# Tail_lights4.net
KiCad netlist of a schematic drawn in EAGLE
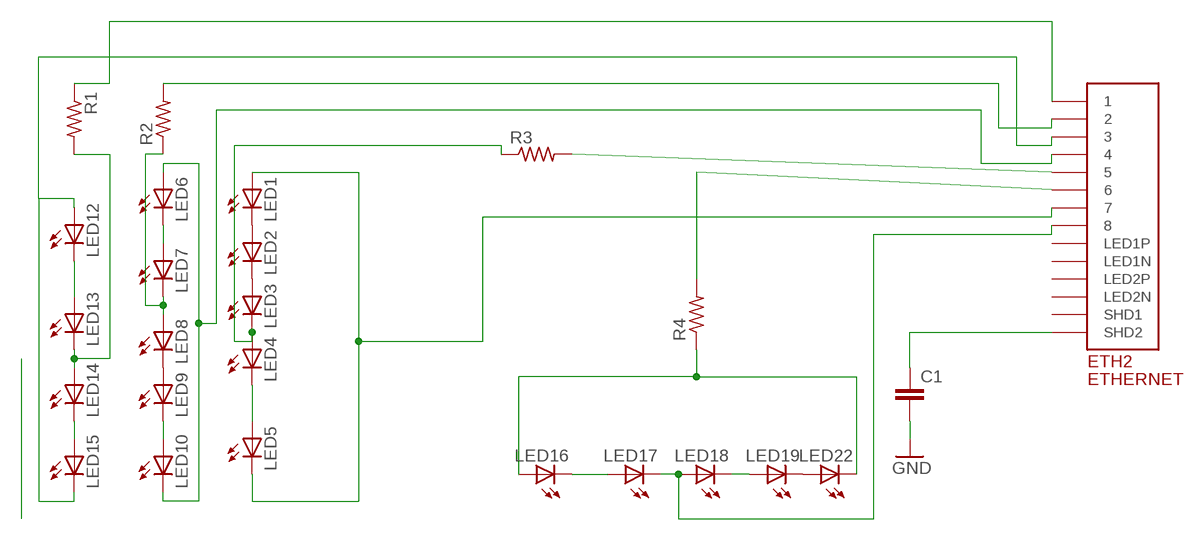
[diagram p0: schematic, sheet 1]

(export (version "E")
  (design (tool "Eeschema 10.0.6"))
  (components
    (comp (ref "C1")
      (value "C2,5-3")
      (footprint "eagle-import:C2.5-3")
      (libsource (lib "eagle-import") (part "C2,5-3"))
    )
    (comp (ref "ETH2")
      (value "ETHERNET")
      (footprint "eagle-import:A122645-ND")
      (libsource (lib "eagle-import") (part "ETHERNET"))
    )
    (comp (ref "LED1")
      (value "LED")
      (footprint "eagle-import:SMARTLED-TTW")
      (libsource (lib "eagle-import") (part "LED"))
    )
    (comp (ref "LED2")
      (value "LED")
      (footprint "eagle-import:SMARTLED-TTW")
      (libsource (lib "eagle-import") (part "LED"))
    )
    (comp (ref "LED3")
      (value "LED")
      (footprint "eagle-import:SMARTLED-TTW")
      (libsource (lib "eagle-import") (part "LED"))
    )
    (comp (ref "LED4")
      (value "LED")
      (footprint "eagle-import:SMARTLED-TTW")
      (libsource (lib "eagle-import") (part "LED"))
    )
    (comp (ref "LED5")
      (value "LED")
      (footprint "eagle-import:SMARTLED-TTW")
      (libsource (lib "eagle-import") (part "LED"))
    )
    (comp (ref "LED6")
      (value "LED")
      (footprint "eagle-import:SMARTLED-TTW")
      (libsource (lib "eagle-import") (part "LED"))
    )
    (comp (ref "LED7")
      (value "LED")
      (footprint "eagle-import:SMARTLED-TTW")
      (libsource (lib "eagle-import") (part "LED"))
    )
    (comp (ref "LED8")
      (value "LED")
      (footprint "eagle-import:SMARTLED-TTW")
      (libsource (lib "eagle-import") (part "LED"))
    )
    (comp (ref "LED9")
      (value "LED")
      (footprint "eagle-import:SMARTLED-TTW")
      (libsource (lib "eagle-import") (part "LED"))
    )
    (comp (ref "LED10")
      (value "LED")
      (footprint "eagle-import:SMARTLED-TTW")
      (libsource (lib "eagle-import") (part "LED"))
    )
    (comp (ref "LED12")
      (value "LED")
      (footprint "eagle-import:SMARTLED-TTW")
      (libsource (lib "eagle-import") (part "LED"))
    )
    (comp (ref "LED13")
      (value "LED")
      (footprint "eagle-import:SMARTLED-TTW")
      (libsource (lib "eagle-import") (part "LED"))
    )
    (comp (ref "LED14")
      (value "LED")
      (footprint "eagle-import:SMARTLED-TTW")
      (libsource (lib "eagle-import") (part "LED"))
    )
    (comp (ref "LED15")
      (value "LED")
      (footprint "eagle-import:SMARTLED-TTW")
      (libsource (lib "eagle-import") (part "LED"))
    )
    (comp (ref "LED16")
      (value "LED")
      (footprint "eagle-import:SMARTLED-TTW")
      (libsource (lib "eagle-import") (part "LED"))
    )
    (comp (ref "LED17")
      (value "LED")
      (footprint "eagle-import:SMARTLED-TTW")
      (libsource (lib "eagle-import") (part "LED"))
    )
    (comp (ref "LED18")
      (value "LED")
      (footprint "eagle-import:SMARTLED-TTW")
      (libsource (lib "eagle-import") (part "LED"))
    )
    (comp (ref "LED19")
      (value "LED")
      (footprint "eagle-import:SMARTLED-TTW")
      (libsource (lib "eagle-import") (part "LED"))
    )
    (comp (ref "LED22")
      (value "LED")
      (footprint "eagle-import:SMARTLED-TTW")
      (libsource (lib "eagle-import") (part "LED"))
    )
    (comp (ref "R1")
      (value "R-US_0204/5")
      (footprint "eagle-import:0204_5")
      (libsource (lib "eagle-import") (part "R-US_0204/5"))
    )
    (comp (ref "R2")
      (value "R-US_0204/2V")
      (footprint "eagle-import:0204V")
      (libsource (lib "eagle-import") (part "R-US_0204/2V"))
    )
    (comp (ref "R3")
      (value "R-US_0204/2V")
      (footprint "eagle-import:0204V")
      (libsource (lib "eagle-import") (part "R-US_0204/2V"))
    )
    (comp (ref "R4")
      (value "R-US_0204/2V")
      (footprint "eagle-import:0204V")
      (libsource (lib "eagle-import") (part "R-US_0204/2V"))
    )
  )
  (nets
    (net (code "1") (name "GND") (class "Default")
      (node (ref "C1") (pin "2") (pinfunction "2_2") (pintype "passive"))
    )
    (net (code "2") (name "Net-(ETH2-1)") (class "Default")
      (node (ref "ETH2") (pin "P$1") (pinfunction "1_P$1") (pintype "bidirectional"))
      (node (ref "R1") (pin "1") (pinfunction "1_1") (pintype "passive"))
    )
    (net (code "3") (name "Net-(ETH2-2)") (class "Default")
      (node (ref "ETH2") (pin "P$2") (pinfunction "2_P$2") (pintype "bidirectional"))
      (node (ref "R2") (pin "2") (pinfunction "2_2") (pintype "passive"))
    )
    (net (code "4") (name "Net-(ETH2-3)") (class "Default")
      (node (ref "ETH2") (pin "P$3") (pinfunction "3_P$3") (pintype "bidirectional"))
      (node (ref "LED12") (pin "A@1") (pinfunction "A_A@1") (pintype "passive"))
      (node (ref "LED15") (pin "C@1") (pinfunction "C_C@1") (pintype "passive"))
    )
    (net (code "5") (name "Net-(ETH2-4)") (class "Default")
      (node (ref "ETH2") (pin "P$4") (pinfunction "4_P$4") (pintype "bidirectional"))
      (node (ref "LED10") (pin "C@1") (pinfunction "C_C@1") (pintype "passive"))
      (node (ref "LED6") (pin "A@1") (pinfunction "A_A@1") (pintype "passive"))
    )
    (net (code "6") (name "Net-(ETH2-5)") (class "Default")
      (node (ref "ETH2") (pin "P$5") (pinfunction "5_P$5") (pintype "bidirectional"))
      (node (ref "R3") (pin "2") (pinfunction "2_2") (pintype "passive"))
    )
    (net (code "7") (name "Net-(ETH2-6)") (class "Default")
      (node (ref "ETH2") (pin "P$6") (pinfunction "6_P$6") (pintype "bidirectional"))
      (node (ref "R4") (pin "2") (pinfunction "2_2") (pintype "passive"))
    )
    (net (code "8") (name "Net-(ETH2-7)") (class "Default")
      (node (ref "ETH2") (pin "P$7") (pinfunction "7_P$7") (pintype "bidirectional"))
      (node (ref "LED1") (pin "A@1") (pinfunction "A_A@1") (pintype "passive"))
      (node (ref "LED5") (pin "C@1") (pinfunction "C_C@1") (pintype "passive"))
    )
    (net (code "9") (name "Net-(ETH2-8)") (class "Default")
      (node (ref "ETH2") (pin "P$8") (pinfunction "8_P$8") (pintype "bidirectional"))
      (node (ref "LED17") (pin "C@1") (pinfunction "C_C@1") (pintype "passive"))
      (node (ref "LED18") (pin "A@1") (pinfunction "A_A@1") (pintype "passive"))
    )
    (net (code "10") (name "Net-(ETH2-SHD2)") (class "Default")
      (node (ref "C1") (pin "1") (pinfunction "1_1") (pintype "passive"))
      (node (ref "ETH2") (pin "P$14") (pinfunction "SHD2_P$14") (pintype "bidirectional"))
    )
    (net (code "11") (name "Net-(LED1-C)") (class "Default")
      (node (ref "LED1") (pin "C@1") (pinfunction "C_C@1") (pintype "passive"))
      (node (ref "LED2") (pin "A@1") (pinfunction "A_A@1") (pintype "passive"))
    )
    (net (code "12") (name "Net-(LED2-C)") (class "Default")
      (node (ref "LED2") (pin "C@1") (pinfunction "C_C@1") (pintype "passive"))
      (node (ref "LED3") (pin "A@1") (pinfunction "A_A@1") (pintype "passive"))
    )
    (net (code "13") (name "Net-(LED3-C)") (class "Default")
      (node (ref "LED3") (pin "C@1") (pinfunction "C_C@1") (pintype "passive"))
      (node (ref "LED4") (pin "A@1") (pinfunction "A_A@1") (pintype "passive"))
      (node (ref "R3") (pin "1") (pinfunction "1_1") (pintype "passive"))
    )
    (net (code "14") (name "Net-(LED4-C)") (class "Default")
      (node (ref "LED4") (pin "C@1") (pinfunction "C_C@1") (pintype "passive"))
      (node (ref "LED5") (pin "A@1") (pinfunction "A_A@1") (pintype "passive"))
    )
    (net (code "15") (name "Net-(LED6-C)") (class "Default")
      (node (ref "LED6") (pin "C@1") (pinfunction "C_C@1") (pintype "passive"))
      (node (ref "LED7") (pin "A@1") (pinfunction "A_A@1") (pintype "passive"))
    )
    (net (code "16") (name "Net-(LED7-C)") (class "Default")
      (node (ref "LED7") (pin "C@1") (pinfunction "C_C@1") (pintype "passive"))
      (node (ref "LED8") (pin "A@1") (pinfunction "A_A@1") (pintype "passive"))
      (node (ref "R2") (pin "1") (pinfunction "1_1") (pintype "passive"))
    )
    (net (code "17") (name "Net-(LED8-C)") (class "Default")
      (node (ref "LED8") (pin "C@1") (pinfunction "C_C@1") (pintype "passive"))
      (node (ref "LED9") (pin "A@1") (pinfunction "A_A@1") (pintype "passive"))
    )
    (net (code "18") (name "Net-(LED10-A)") (class "Default")
      (node (ref "LED10") (pin "A@1") (pinfunction "A_A@1") (pintype "passive"))
      (node (ref "LED9") (pin "C@1") (pinfunction "C_C@1") (pintype "passive"))
    )
    (net (code "19") (name "Net-(LED12-C)") (class "Default")
      (node (ref "LED12") (pin "C@1") (pinfunction "C_C@1") (pintype "passive"))
      (node (ref "LED13") (pin "A@1") (pinfunction "A_A@1") (pintype "passive"))
    )
    (net (code "20") (name "Net-(LED13-C)") (class "Default")
      (node (ref "LED13") (pin "C@1") (pinfunction "C_C@1") (pintype "passive"))
      (node (ref "LED14") (pin "A@1") (pinfunction "A_A@1") (pintype "passive"))
      (node (ref "R1") (pin "2") (pinfunction "2_2") (pintype "passive"))
    )
    (net (code "21") (name "Net-(LED14-C)") (class "Default")
      (node (ref "LED14") (pin "C@1") (pinfunction "C_C@1") (pintype "passive"))
      (node (ref "LED15") (pin "A@1") (pinfunction "A_A@1") (pintype "passive"))
    )
    (net (code "22") (name "Net-(LED16-A)") (class "Default")
      (node (ref "LED16") (pin "A@1") (pinfunction "A_A@1") (pintype "passive"))
      (node (ref "LED22") (pin "C@1") (pinfunction "C_C@1") (pintype "passive"))
      (node (ref "R4") (pin "1") (pinfunction "1_1") (pintype "passive"))
    )
    (net (code "23") (name "Net-(LED16-C)") (class "Default")
      (node (ref "LED16") (pin "C@1") (pinfunction "C_C@1") (pintype "passive"))
      (node (ref "LED17") (pin "A@1") (pinfunction "A_A@1") (pintype "passive"))
    )
    (net (code "24") (name "Net-(LED18-C)") (class "Default")
      (node (ref "LED18") (pin "C@1") (pinfunction "C_C@1") (pintype "passive"))
      (node (ref "LED19") (pin "A@1") (pinfunction "A_A@1") (pintype "passive"))
    )
    (net (code "25") (name "Net-(LED19-C)") (class "Default")
      (node (ref "LED19") (pin "C@1") (pinfunction "C_C@1") (pintype "passive"))
      (node (ref "LED22") (pin "A@1") (pinfunction "A_A@1") (pintype "passive"))
    )
    (net (code "26") (name "unconnected-(ETH2-LED1N-PadP$9)") (class "Default")
      (node (ref "ETH2") (pin "P$9") (pinfunction "LED1N_P$9") (pintype "bidirectional"))
    )
    (net (code "27") (name "unconnected-(ETH2-LED1P-PadP$10)") (class "Default")
      (node (ref "ETH2") (pin "P$10") (pinfunction "LED1P_P$10") (pintype "bidirectional"))
    )
    (net (code "28") (name "unconnected-(ETH2-LED2N-PadP$11)") (class "Default")
      (node (ref "ETH2") (pin "P$11") (pinfunction "LED2N_P$11") (pintype "bidirectional"))
    )
    (net (code "29") (name "unconnected-(ETH2-LED2P-PadP$12)") (class "Default")
      (node (ref "ETH2") (pin "P$12") (pinfunction "LED2P_P$12") (pintype "bidirectional"))
    )
    (net (code "30") (name "unconnected-(ETH2-SHD1-PadP$13)") (class "Default")
      (node (ref "ETH2") (pin "P$13") (pinfunction "SHD1_P$13") (pintype "bidirectional"))
    )
  )
)
